# MLX90640_Sheet.net
KiCad netlist of a schematic drawn in Altium Designer
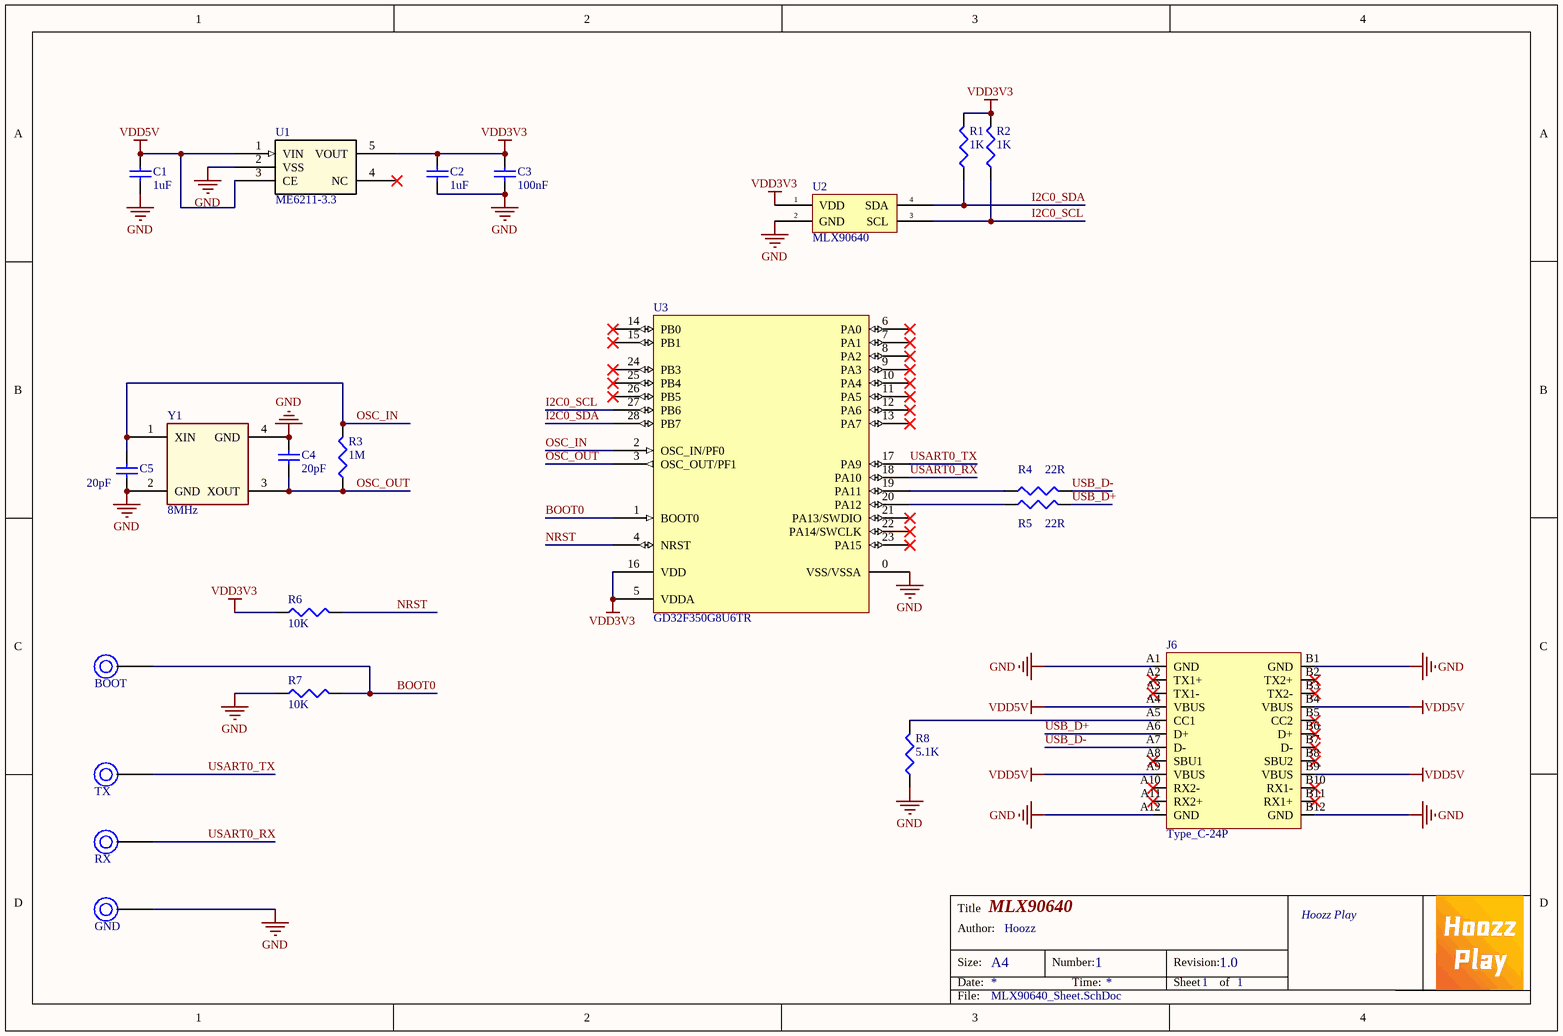
[diagram p0: MLX90640_Sheet.SchDoc]

(export (version "E")
  (design (tool "Eeschema 10.0.6"))
  (components
    (comp (ref "BOOT")
      (value "TEST-PORT")
      (footprint "TEST-PORT")
      (libsource (lib "CORE_COMPONENT") (part "TEST-PORT"))
    )
    (comp (ref "C1")
      (value "1uF")
      (footprint "0603")
      (description "Capacitor")
      (fields (field (name "Comment") "Cap") (field (name "PUBLISHER") "Altium Limited"))
      (libsource (lib "CORE_COMPONENT") (part "Cap"))
    )
    (comp (ref "C2")
      (value "1uF")
      (footprint "0603")
      (description "Capacitor")
      (fields (field (name "Comment") "Cap") (field (name "PUBLISHER") "Altium Limited"))
      (libsource (lib "CORE_COMPONENT") (part "Cap"))
    )
    (comp (ref "C3")
      (value "100nF")
      (footprint "0603")
      (description "Capacitor")
      (fields (field (name "Comment") "Cap") (field (name "PUBLISHER") "Altium Limited"))
      (libsource (lib "CORE_COMPONENT") (part "Cap"))
    )
    (comp (ref "C4")
      (value "20pF")
      (footprint "0603")
      (description "Capacitor")
      (fields (field (name "Comment") "Cap") (field (name "PUBLISHER") "Altium Limited"))
      (libsource (lib "CORE_COMPONENT") (part "Cap"))
    )
    (comp (ref "C5")
      (value "20pF")
      (footprint "0603")
      (description "Capacitor")
      (fields (field (name "Comment") "Cap") (field (name "PUBLISHER") "Altium Limited"))
      (libsource (lib "CORE_COMPONENT") (part "Cap"))
    )
    (comp (ref "GND")
      (value "TEST-PORT")
      (footprint "TEST-PORT")
      (libsource (lib "CORE_COMPONENT") (part "TEST-PORT"))
    )
    (comp (ref "J6")
      (value "Type_C-24P")
      (footprint "Type_C-24P-A")
      (description "USB Type C")
      (libsource (lib "CORE_COMPONENT") (part "Type_C-24P"))
    )
    (comp (ref "R1")
      (value "1K")
      (footprint "0603")
      (description "Resistor")
      (fields (field (name "Comment") "Res") (field (name "PUBLISHER") "Altium Limited"))
      (libsource (lib "CORE_COMPONENT") (part "Res"))
    )
    (comp (ref "R2")
      (value "1K")
      (footprint "0603")
      (description "Resistor")
      (fields (field (name "Comment") "Res") (field (name "PUBLISHER") "Altium Limited"))
      (libsource (lib "CORE_COMPONENT") (part "Res"))
    )
    (comp (ref "R3")
      (value "1M")
      (footprint "0603")
      (description "Resistor")
      (fields (field (name "Comment") "Res") (field (name "PUBLISHER") "Altium Limited"))
      (libsource (lib "CORE_COMPONENT") (part "Res"))
    )
    (comp (ref "R4")
      (value "22R")
      (footprint "0603")
      (description "Resistor")
      (fields (field (name "Comment") "Res") (field (name "PUBLISHER") "Altium Limited"))
      (libsource (lib "CORE_COMPONENT") (part "Res"))
    )
    (comp (ref "R5")
      (value "22R")
      (footprint "0603")
      (description "Resistor")
      (fields (field (name "Comment") "Res") (field (name "PUBLISHER") "Altium Limited"))
      (libsource (lib "CORE_COMPONENT") (part "Res"))
    )
    (comp (ref "R6")
      (value "10K")
      (footprint "0603")
      (description "Resistor")
      (fields (field (name "Comment") "Res") (field (name "PUBLISHER") "Altium Limited"))
      (libsource (lib "CORE_COMPONENT") (part "Res"))
    )
    (comp (ref "R7")
      (value "10K")
      (footprint "0603")
      (description "Resistor")
      (fields (field (name "Comment") "Res") (field (name "PUBLISHER") "Altium Limited"))
      (libsource (lib "CORE_COMPONENT") (part "Res"))
    )
    (comp (ref "R8")
      (value "5.1K")
      (footprint "0603")
      (description "Resistor")
      (fields (field (name "Comment") "Res") (field (name "PUBLISHER") "Altium Limited"))
      (libsource (lib "CORE_COMPONENT") (part "Res"))
    )
    (comp (ref "RX")
      (value "TEST-PORT")
      (footprint "TEST-PORT")
      (libsource (lib "CORE_COMPONENT") (part "TEST-PORT"))
    )
    (comp (ref "TX")
      (value "TEST-PORT")
      (footprint "TEST-PORT")
      (libsource (lib "CORE_COMPONENT") (part "TEST-PORT"))
    )
    (comp (ref "U1")
      (value "ME6211-3.3")
      (footprint "SOT-23-5")
      (description "No Description Available")
      (fields
        (field (name "MANUFACTURER") "Texas Instruments")
        (field (name "MANUFACTURER_PART_NUMBER") "REG102NA-2.5/250")
        (field (name "COPYRIGHT") "Copyright (C) 2018 Accelerated Designs. All rights reserved")
      )
      (libsource (lib "CORE_COMPONENT") (part "ME6211-3.3"))
    )
    (comp (ref "U2")
      (value "MLX90640")
      (footprint "MLX90640")
      (libsource (lib "CORE_COMPONENT") (part "MLX90640"))
    )
    (comp (ref "U3")
      (value "GD32F350G8U6TR")
      (footprint "QFN28_4X4X0.8")
      (libsource (lib "GD-MCU") (part "GD32F350GxUx"))
    )
    (comp (ref "Y1") (value "8MHz") (footprint "3225") (libsource (lib "CORE_COMPONENT") (part "XTAL2")))
  )
  (nets
    (net (code "1") (name "/BOOT0") (class "Default")
      (node (ref "BOOT") (pin "T") (pintype "passive"))
      (node (ref "R7") (pin "2") (pinfunction "2_2") (pintype "passive"))
      (node (ref "U3") (pin "1") (pinfunction "BOOT0_1") (pintype "input"))
    )
    (net (code "2") (name "/I2C0_SCL") (class "Default")
      (node (ref "R2") (pin "1") (pinfunction "1_1") (pintype "passive"))
      (node (ref "U2") (pin "3") (pinfunction "SCL_3") (pintype "passive"))
      (node (ref "U3") (pin "27") (pinfunction "PB6_27") (pintype "bidirectional"))
    )
    (net (code "3") (name "/I2C0_SDA") (class "Default")
      (node (ref "R1") (pin "1") (pinfunction "1_1") (pintype "passive"))
      (node (ref "U2") (pin "4") (pinfunction "SDA_4") (pintype "passive"))
      (node (ref "U3") (pin "28") (pinfunction "PB7_28") (pintype "bidirectional"))
    )
    (net (code "4") (name "/NRST") (class "Default")
      (node (ref "R6") (pin "2") (pinfunction "2_2") (pintype "passive"))
      (node (ref "U3") (pin "4") (pinfunction "NRST_4") (pintype "bidirectional"))
    )
    (net (code "5") (name "/OSC_IN") (class "Default")
      (node (ref "C5") (pin "2") (pinfunction "2_2") (pintype "passive"))
      (node (ref "R3") (pin "2") (pinfunction "2_2") (pintype "passive"))
      (node (ref "U3") (pin "2") (pinfunction "OSC_IN/PF0_2") (pintype "input"))
      (node (ref "Y1") (pin "1") (pinfunction "XIN_1") (pintype "passive"))
    )
    (net (code "6") (name "/OSC_OUT") (class "Default")
      (node (ref "C4") (pin "1") (pinfunction "1_1") (pintype "passive"))
      (node (ref "R3") (pin "1") (pinfunction "1_1") (pintype "passive"))
      (node (ref "U3") (pin "3") (pinfunction "OSC_OUT/PF1_3") (pintype "output"))
      (node (ref "Y1") (pin "3") (pinfunction "XOUT_3") (pintype "passive"))
    )
    (net (code "7") (name "/USART0_RX") (class "Default")
      (node (ref "RX") (pin "T") (pintype "passive"))
      (node (ref "U3") (pin "18") (pinfunction "PA10_18") (pintype "bidirectional"))
    )
    (net (code "8") (name "/USART0_TX") (class "Default")
      (node (ref "TX") (pin "T") (pintype "passive"))
      (node (ref "U3") (pin "17") (pinfunction "PA9_17") (pintype "bidirectional"))
    )
    (net (code "9") (name "/USB_D+") (class "Default")
      (node (ref "J6") (pin "A6") (pinfunction "D+_A6") (pintype "passive"))
      (node (ref "R5") (pin "2") (pinfunction "2_2") (pintype "passive"))
    )
    (net (code "10") (name "/USB_D-") (class "Default")
      (node (ref "J6") (pin "A7") (pinfunction "D-_A7") (pintype "passive"))
      (node (ref "R4") (pin "2") (pinfunction "2_2") (pintype "passive"))
    )
    (net (code "11") (name "GND") (class "Default")
      (node (ref "C1") (pin "1") (pinfunction "1_1") (pintype "passive"))
      (node (ref "C2") (pin "1") (pinfunction "1_1") (pintype "passive"))
      (node (ref "C3") (pin "1") (pinfunction "1_1") (pintype "passive"))
      (node (ref "C4") (pin "2") (pinfunction "2_2") (pintype "passive"))
      (node (ref "C5") (pin "1") (pinfunction "1_1") (pintype "passive"))
      (node (ref "GND") (pin "T") (pintype "passive"))
      (node (ref "J6") (pin "A1") (pinfunction "GND_A1") (pintype "passive"))
      (node (ref "J6") (pin "A12") (pinfunction "GND_A12") (pintype "passive"))
      (node (ref "J6") (pin "B1") (pinfunction "GND_B1") (pintype "passive"))
      (node (ref "J6") (pin "B12") (pinfunction "GND_B12") (pintype "passive"))
      (node (ref "R7") (pin "1") (pinfunction "1_1") (pintype "passive"))
      (node (ref "R8") (pin "1") (pinfunction "1_1") (pintype "passive"))
      (node (ref "U1") (pin "2") (pinfunction "VSS_2") (pintype "power_in"))
      (node (ref "U2") (pin "2") (pinfunction "GND_2") (pintype "passive"))
      (node (ref "U3") (pin "0") (pinfunction "VSS/VSSA_0") (pintype "power_in"))
      (node (ref "Y1") (pin "2") (pinfunction "GND_2") (pintype "power_in"))
      (node (ref "Y1") (pin "4") (pinfunction "GND_4") (pintype "power_in"))
    )
    (net (code "12") (name "Net-(J6-CC1)") (class "Default")
      (node (ref "J6") (pin "A5") (pinfunction "CC1_A5") (pintype "passive"))
      (node (ref "R8") (pin "2") (pinfunction "2_2") (pintype "passive"))
    )
    (net (code "13") (name "Net-(U3-PA11)") (class "Default")
      (node (ref "R4") (pin "1") (pinfunction "1_1") (pintype "passive"))
      (node (ref "U3") (pin "19") (pinfunction "PA11_19") (pintype "bidirectional"))
    )
    (net (code "14") (name "Net-(U3-PA12)") (class "Default")
      (node (ref "R5") (pin "1") (pinfunction "1_1") (pintype "passive"))
      (node (ref "U3") (pin "20") (pinfunction "PA12_20") (pintype "bidirectional"))
    )
    (net (code "15") (name "VDD3V3") (class "Default")
      (node (ref "C2") (pin "2") (pinfunction "2_2") (pintype "passive"))
      (node (ref "C3") (pin "2") (pinfunction "2_2") (pintype "passive"))
      (node (ref "R1") (pin "2") (pinfunction "2_2") (pintype "passive"))
      (node (ref "R2") (pin "2") (pinfunction "2_2") (pintype "passive"))
      (node (ref "R6") (pin "1") (pinfunction "1_1") (pintype "passive"))
      (node (ref "U1") (pin "5") (pinfunction "VOUT_5") (pintype "passive"))
      (node (ref "U2") (pin "1") (pinfunction "VDD_1") (pintype "passive"))
      (node (ref "U3") (pin "16") (pinfunction "VDD_16") (pintype "power_in"))
      (node (ref "U3") (pin "5") (pinfunction "VDDA_5") (pintype "power_in"))
    )
    (net (code "16") (name "VDD5V") (class "Default")
      (node (ref "C1") (pin "2") (pinfunction "2_2") (pintype "passive"))
      (node (ref "J6") (pin "A4") (pinfunction "VBUS_A4") (pintype "passive"))
      (node (ref "J6") (pin "A9") (pinfunction "VBUS_A9") (pintype "passive"))
      (node (ref "J6") (pin "B4") (pinfunction "VBUS_B4") (pintype "passive"))
      (node (ref "J6") (pin "B9") (pinfunction "VBUS_B9") (pintype "passive"))
      (node (ref "U1") (pin "1") (pinfunction "VIN_1") (pintype "input"))
      (node (ref "U1") (pin "3") (pinfunction "CE_3") (pintype "passive"))
    )
    (net (code "17") (name "unconnected-(J6-CC2-PadB5)") (class "Default")
      (node (ref "J6") (pin "B5") (pinfunction "CC2_B5") (pintype "passive+no_connect"))
    )
    (net (code "18") (name "unconnected-(J6-D+-PadB6)") (class "Default")
      (node (ref "J6") (pin "B6") (pinfunction "D+_B6") (pintype "passive+no_connect"))
    )
    (net (code "19") (name "unconnected-(J6-D--PadB7)") (class "Default")
      (node (ref "J6") (pin "B7") (pinfunction "D-_B7") (pintype "passive+no_connect"))
    )
    (net (code "20") (name "unconnected-(J6-RX1+-PadB11)") (class "Default")
      (node (ref "J6") (pin "B11") (pinfunction "RX1+_B11") (pintype "passive+no_connect"))
    )
    (net (code "21") (name "unconnected-(J6-RX1--PadB10)") (class "Default")
      (node (ref "J6") (pin "B10") (pinfunction "RX1-_B10") (pintype "passive+no_connect"))
    )
    (net (code "22") (name "unconnected-(J6-RX2+-PadA11)") (class "Default")
      (node (ref "J6") (pin "A11") (pinfunction "RX2+_A11") (pintype "passive+no_connect"))
    )
    (net (code "23") (name "unconnected-(J6-RX2--PadA10)") (class "Default")
      (node (ref "J6") (pin "A10") (pinfunction "RX2-_A10") (pintype "passive+no_connect"))
    )
    (net (code "24") (name "unconnected-(J6-SBU1-PadA8)") (class "Default")
      (node (ref "J6") (pin "A8") (pinfunction "SBU1_A8") (pintype "passive+no_connect"))
    )
    (net (code "25") (name "unconnected-(J6-SBU2-PadB8)") (class "Default")
      (node (ref "J6") (pin "B8") (pinfunction "SBU2_B8") (pintype "passive+no_connect"))
    )
    (net (code "26") (name "unconnected-(J6-TX1+-PadA2)") (class "Default")
      (node (ref "J6") (pin "A2") (pinfunction "TX1+_A2") (pintype "passive+no_connect"))
    )
    (net (code "27") (name "unconnected-(J6-TX1--PadA3)") (class "Default")
      (node (ref "J6") (pin "A3") (pinfunction "TX1-_A3") (pintype "passive+no_connect"))
    )
    (net (code "28") (name "unconnected-(J6-TX2+-PadB2)") (class "Default")
      (node (ref "J6") (pin "B2") (pinfunction "TX2+_B2") (pintype "passive+no_connect"))
    )
    (net (code "29") (name "unconnected-(J6-TX2--PadB3)") (class "Default")
      (node (ref "J6") (pin "B3") (pinfunction "TX2-_B3") (pintype "passive+no_connect"))
    )
    (net (code "30") (name "unconnected-(U1-NC-Pad4)") (class "Default")
      (node (ref "U1") (pin "4") (pinfunction "NC_4") (pintype "passive+no_connect"))
    )
    (net (code "31") (name "unconnected-(U3-PA0-Pad6)") (class "Default")
      (node (ref "U3") (pin "6") (pinfunction "PA0_6") (pintype "bidirectional+no_connect"))
    )
    (net (code "32") (name "unconnected-(U3-PA1-Pad7)") (class "Default")
      (node (ref "U3") (pin "7") (pinfunction "PA1_7") (pintype "bidirectional+no_connect"))
    )
    (net (code "33") (name "unconnected-(U3-PA2-Pad8)") (class "Default")
      (node (ref "U3") (pin "8") (pinfunction "PA2_8") (pintype "bidirectional+no_connect"))
    )
    (net (code "34") (name "unconnected-(U3-PA3-Pad9)") (class "Default")
      (node (ref "U3") (pin "9") (pinfunction "PA3_9") (pintype "bidirectional+no_connect"))
    )
    (net (code "35") (name "unconnected-(U3-PA4-Pad10)") (class "Default")
      (node (ref "U3") (pin "10") (pinfunction "PA4_10") (pintype "bidirectional+no_connect"))
    )
    (net (code "36") (name "unconnected-(U3-PA5-Pad11)") (class "Default")
      (node (ref "U3") (pin "11") (pinfunction "PA5_11") (pintype "bidirectional+no_connect"))
    )
    (net (code "37") (name "unconnected-(U3-PA6-Pad12)") (class "Default")
      (node (ref "U3") (pin "12") (pinfunction "PA6_12") (pintype "bidirectional+no_connect"))
    )
    (net (code "38") (name "unconnected-(U3-PA7-Pad13)") (class "Default")
      (node (ref "U3") (pin "13") (pinfunction "PA7_13") (pintype "bidirectional+no_connect"))
    )
    (net (code "39") (name "unconnected-(U3-PA13{slash}SWDIO-Pad21)") (class "Default")
      (node (ref "U3") (pin "21") (pinfunction "PA13/SWDIO_21") (pintype "bidirectional+no_connect"))
    )
    (net (code "40") (name "unconnected-(U3-PA14{slash}SWCLK-Pad22)") (class "Default")
      (node (ref "U3") (pin "22") (pinfunction "PA14/SWCLK_22") (pintype "bidirectional+no_connect"))
    )
    (net (code "41") (name "unconnected-(U3-PA15-Pad23)") (class "Default")
      (node (ref "U3") (pin "23") (pinfunction "PA15_23") (pintype "bidirectional+no_connect"))
    )
    (net (code "42") (name "unconnected-(U3-PB0-Pad14)") (class "Default")
      (node (ref "U3") (pin "14") (pinfunction "PB0_14") (pintype "bidirectional+no_connect"))
    )
    (net (code "43") (name "unconnected-(U3-PB1-Pad15)") (class "Default")
      (node (ref "U3") (pin "15") (pinfunction "PB1_15") (pintype "bidirectional+no_connect"))
    )
    (net (code "44") (name "unconnected-(U3-PB3-Pad24)") (class "Default")
      (node (ref "U3") (pin "24") (pinfunction "PB3_24") (pintype "bidirectional+no_connect"))
    )
    (net (code "45") (name "unconnected-(U3-PB4-Pad25)") (class "Default")
      (node (ref "U3") (pin "25") (pinfunction "PB4_25") (pintype "bidirectional+no_connect"))
    )
    (net (code "46") (name "unconnected-(U3-PB5-Pad26)") (class "Default")
      (node (ref "U3") (pin "26") (pinfunction "PB5_26") (pintype "bidirectional+no_connect"))
    )
  )
)
